# Cloud_Upload.net
KiCad netlist of a schematic drawn in Altium Designer
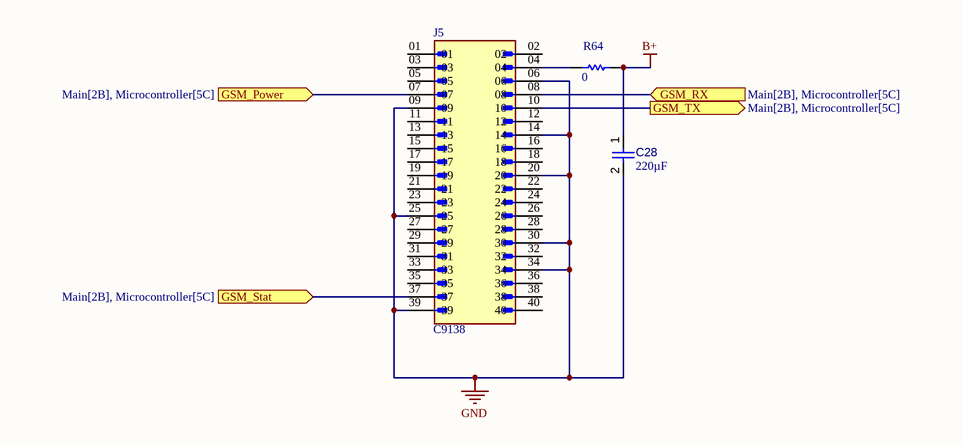
[diagram p0: Cloud Upload.SchDoc]

(export (version "E")
  (design (tool "Eeschema 10.0.6"))
  (components
    (comp (ref "C28")
      (value "220µF")
      (footprint "FP-FTD8-MFG")
      (description "Radial Can - SMD ALUMINUM ELECTROLYTIC CAPACITOR FT 25V 220muF 卤20% 0.248Dia 6.30mm")
      (fields (field (name "TOLERANCE") "20%") (field (name "Comment") "EEEFTE221XAP"))
      (libsource (lib "Buddhi Rashmika") (part "CAP-NP-2"))
    )
    (comp (ref "J5")
      (value "C9138")
      (footprint "AMPHENOL_10129381-940001BLF")
      (fields (field (name "MF") "Amphenol ICC (FCI)") (field (name "MP") "10129381-940001BLF"))
      (libsource (lib "Buddhi Rashmika") (part "10129381-940001BLF"))
    )
    (comp (ref "R64")
      (value "0")
      (footprint "RESC1608X55X25ML10T15")
      (description "Chip Resistor, 0 Ohm, 0.1 W, -55 to 155 degC, 0603 (1608 Metric)")
      (fields (field (name "POWER") "100mW") (field (name "TOLERANCE") "5%"))
      (libsource (lib "Buddhi Rashmika") (part "RES-2"))
    )
  )
  (nets
    (net (code "1") (name "/GSM_Power") (class "Default")
      (node (ref "J5") (pin "07") (pinfunction "07_07") (pintype "passive"))
    )
    (net (code "2") (name "/GSM_RX") (class "Default")
      (node (ref "J5") (pin "08") (pinfunction "08_08") (pintype "passive"))
    )
    (net (code "3") (name "/GSM_Stat") (class "Default")
      (node (ref "J5") (pin "37") (pinfunction "37_37") (pintype "passive"))
    )
    (net (code "4") (name "/GSM_TX") (class "Default")
      (node (ref "J5") (pin "10") (pinfunction "10_10") (pintype "passive"))
    )
    (net (code "5") (name "B+") (class "Default")
      (node (ref "C28") (pin "1") (pinfunction "1_1") (pintype "passive"))
      (node (ref "R64") (pin "2") (pinfunction "2_2") (pintype "passive"))
    )
    (net (code "6") (name "GND") (class "Default")
      (node (ref "C28") (pin "2") (pinfunction "2_2") (pintype "passive"))
      (node (ref "J5") (pin "06") (pinfunction "06_06") (pintype "passive"))
      (node (ref "J5") (pin "09") (pinfunction "09_09") (pintype "passive"))
      (node (ref "J5") (pin "14") (pinfunction "14_14") (pintype "passive"))
      (node (ref "J5") (pin "20") (pinfunction "20_20") (pintype "passive"))
      (node (ref "J5") (pin "25") (pinfunction "25_25") (pintype "passive"))
      (node (ref "J5") (pin "30") (pinfunction "30_30") (pintype "passive"))
      (node (ref "J5") (pin "34") (pinfunction "34_34") (pintype "passive"))
      (node (ref "J5") (pin "39") (pinfunction "39_39") (pintype "passive"))
    )
    (net (code "7") (name "Net-(J5-Pad04)") (class "Default")
      (node (ref "J5") (pin "04") (pinfunction "04_04") (pintype "passive"))
      (node (ref "R64") (pin "1") (pinfunction "1_1") (pintype "passive"))
    )
    (net (code "8") (name "unconnected-(J5-Pad01)") (class "Default")
      (node (ref "J5") (pin "01") (pinfunction "01_01") (pintype "passive"))
    )
    (net (code "9") (name "unconnected-(J5-Pad02)") (class "Default")
      (node (ref "J5") (pin "02") (pinfunction "02_02") (pintype "passive"))
    )
    (net (code "10") (name "unconnected-(J5-Pad03)") (class "Default")
      (node (ref "J5") (pin "03") (pinfunction "03_03") (pintype "passive"))
    )
    (net (code "11") (name "unconnected-(J5-Pad05)") (class "Default")
      (node (ref "J5") (pin "05") (pinfunction "05_05") (pintype "passive"))
    )
    (net (code "12") (name "unconnected-(J5-Pad11)") (class "Default")
      (node (ref "J5") (pin "11") (pinfunction "11_11") (pintype "passive"))
    )
    (net (code "13") (name "unconnected-(J5-Pad12)") (class "Default")
      (node (ref "J5") (pin "12") (pinfunction "12_12") (pintype "passive"))
    )
    (net (code "14") (name "unconnected-(J5-Pad13)") (class "Default")
      (node (ref "J5") (pin "13") (pinfunction "13_13") (pintype "passive"))
    )
    (net (code "15") (name "unconnected-(J5-Pad15)") (class "Default")
      (node (ref "J5") (pin "15") (pinfunction "15_15") (pintype "passive"))
    )
    (net (code "16") (name "unconnected-(J5-Pad16)") (class "Default")
      (node (ref "J5") (pin "16") (pinfunction "16_16") (pintype "passive"))
    )
    (net (code "17") (name "unconnected-(J5-Pad17)") (class "Default")
      (node (ref "J5") (pin "17") (pinfunction "17_17") (pintype "passive"))
    )
    (net (code "18") (name "unconnected-(J5-Pad18)") (class "Default")
      (node (ref "J5") (pin "18") (pinfunction "18_18") (pintype "passive"))
    )
    (net (code "19") (name "unconnected-(J5-Pad19)") (class "Default")
      (node (ref "J5") (pin "19") (pinfunction "19_19") (pintype "passive"))
    )
    (net (code "20") (name "unconnected-(J5-Pad21)") (class "Default")
      (node (ref "J5") (pin "21") (pinfunction "21_21") (pintype "passive"))
    )
    (net (code "21") (name "unconnected-(J5-Pad22)") (class "Default")
      (node (ref "J5") (pin "22") (pinfunction "22_22") (pintype "passive"))
    )
    (net (code "22") (name "unconnected-(J5-Pad23)") (class "Default")
      (node (ref "J5") (pin "23") (pinfunction "23_23") (pintype "passive"))
    )
    (net (code "23") (name "unconnected-(J5-Pad24)") (class "Default")
      (node (ref "J5") (pin "24") (pinfunction "24_24") (pintype "passive"))
    )
    (net (code "24") (name "unconnected-(J5-Pad26)") (class "Default")
      (node (ref "J5") (pin "26") (pinfunction "26_26") (pintype "passive"))
    )
    (net (code "25") (name "unconnected-(J5-Pad27)") (class "Default")
      (node (ref "J5") (pin "27") (pinfunction "27_27") (pintype "passive"))
    )
    (net (code "26") (name "unconnected-(J5-Pad28)") (class "Default")
      (node (ref "J5") (pin "28") (pinfunction "28_28") (pintype "passive"))
    )
    (net (code "27") (name "unconnected-(J5-Pad29)") (class "Default")
      (node (ref "J5") (pin "29") (pinfunction "29_29") (pintype "passive"))
    )
    (net (code "28") (name "unconnected-(J5-Pad31)") (class "Default")
      (node (ref "J5") (pin "31") (pinfunction "31_31") (pintype "passive"))
    )
    (net (code "29") (name "unconnected-(J5-Pad32)") (class "Default")
      (node (ref "J5") (pin "32") (pinfunction "32_32") (pintype "passive"))
    )
    (net (code "30") (name "unconnected-(J5-Pad33)") (class "Default")
      (node (ref "J5") (pin "33") (pinfunction "33_33") (pintype "passive"))
    )
    (net (code "31") (name "unconnected-(J5-Pad35)") (class "Default")
      (node (ref "J5") (pin "35") (pinfunction "35_35") (pintype "passive"))
    )
    (net (code "32") (name "unconnected-(J5-Pad36)") (class "Default")
      (node (ref "J5") (pin "36") (pinfunction "36_36") (pintype "passive"))
    )
    (net (code "33") (name "unconnected-(J5-Pad38)") (class "Default")
      (node (ref "J5") (pin "38") (pinfunction "38_38") (pintype "passive"))
    )
    (net (code "34") (name "unconnected-(J5-Pad40)") (class "Default")
      (node (ref "J5") (pin "40") (pinfunction "40_40") (pintype "passive"))
    )
  )
)
